# PiModulos_-_Mayonaise.net
KiCad netlist of a schematic drawn in Altium Designer
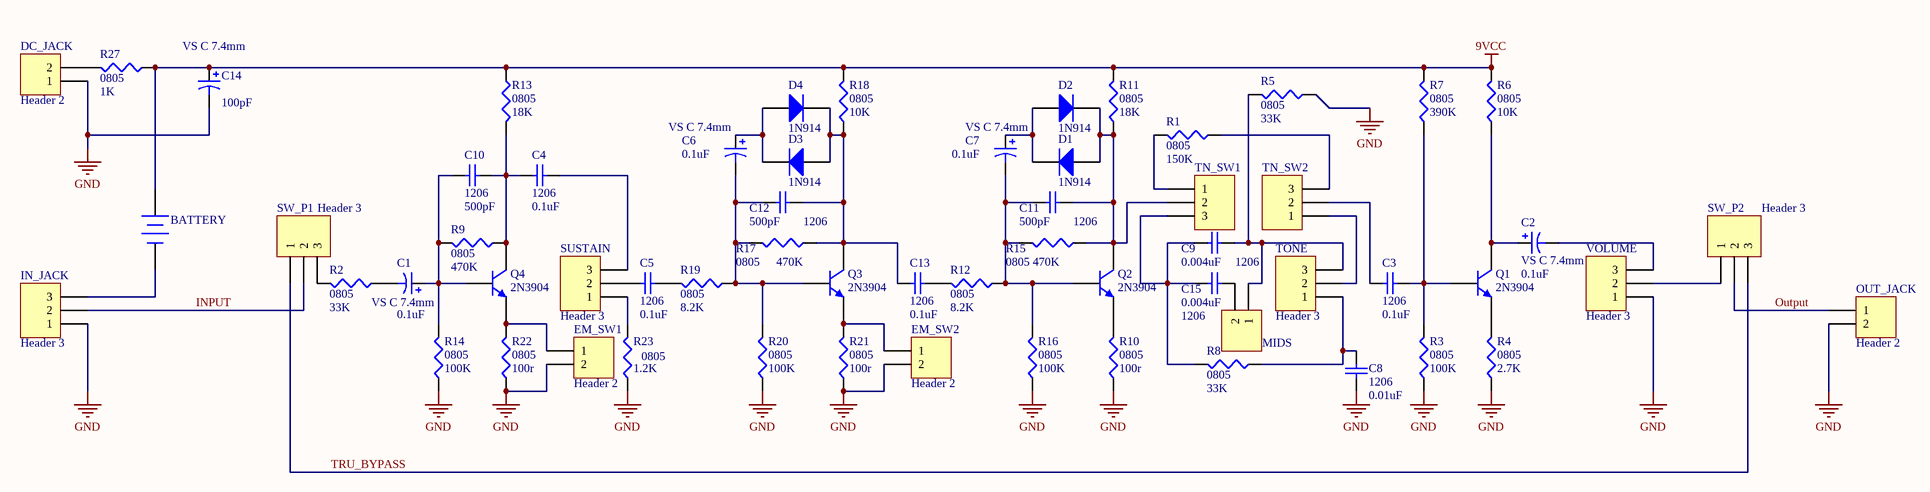
[diagram p0: PiModulos - Mayonaise.SchDoc]

(export (version "E")
  (design (tool "Eeschema 10.0.6"))
  (components
    (comp (ref "BATTERY")
      (value "Battery")
      (footprint "BAT-2")
      (description "Multicell Battery")
      (fields (field (name "PUBLISHER") "Altium Limited"))
      (libsource (lib "Miscellaneous Devices") (part "Battery"))
    )
    (comp (ref "C1")
      (value "VS C 7.4mm")
      (footprint "Panasonic VS C")
      (description "Polarized Capacitor (Radial)")
      (fields (field (name "ALTIUM_VALUE") "0.1uF") (field (name "PUBLISHER") "Altium Limited"))
      (libsource (lib "Miscellaneous Devices") (part "Cap Pol1"))
    )
    (comp (ref "C2")
      (value "VS C 7.4mm")
      (footprint "Panasonic VS C")
      (description "Polarized Capacitor (Radial)")
      (fields (field (name "ALTIUM_VALUE") "0.1uF") (field (name "PUBLISHER") "Altium Limited"))
      (libsource (lib "Miscellaneous Devices") (part "Cap Pol1"))
    )
    (comp (ref "C3")
      (value "1206")
      (footprint "C1206")
      (description "Capacitor (Semiconductor SIM Model)")
      (fields (field (name "ALTIUM_VALUE") "0.1uF") (field (name "PUBLISHER") "Altium Limited"))
      (libsource (lib "Miscellaneous Devices") (part "Cap Semi"))
    )
    (comp (ref "C4")
      (value "1206")
      (footprint "C1206")
      (description "Capacitor (Semiconductor SIM Model)")
      (fields (field (name "ALTIUM_VALUE") "0.1uF") (field (name "PUBLISHER") "Altium Limited"))
      (libsource (lib "Miscellaneous Devices") (part "Cap Semi"))
    )
    (comp (ref "C5")
      (value "1206")
      (footprint "C1206")
      (description "Capacitor (Semiconductor SIM Model)")
      (fields (field (name "ALTIUM_VALUE") "0.1uF") (field (name "PUBLISHER") "Altium Limited"))
      (libsource (lib "Miscellaneous Devices") (part "Cap Semi"))
    )
    (comp (ref "C6")
      (value "VS C 7.4mm")
      (footprint "Panasonic VS C")
      (description "Polarized Capacitor (Radial)")
      (fields (field (name "ALTIUM_VALUE") "0.1uF") (field (name "PUBLISHER") "Altium Limited"))
      (libsource (lib "Miscellaneous Devices") (part "Cap Pol1"))
    )
    (comp (ref "C7")
      (value "VS C 7.4mm")
      (footprint "Panasonic VS C")
      (description "Polarized Capacitor (Radial)")
      (fields (field (name "ALTIUM_VALUE") "0.1uF") (field (name "PUBLISHER") "Altium Limited"))
      (libsource (lib "Miscellaneous Devices") (part "Cap Pol1"))
    )
    (comp (ref "C8")
      (value "1206")
      (footprint "C1206")
      (description "Capacitor (Semiconductor SIM Model)")
      (fields (field (name "ALTIUM_VALUE") "0.01uF") (field (name "PUBLISHER") "Altium Limited"))
      (libsource (lib "Miscellaneous Devices") (part "Cap Semi"))
    )
    (comp (ref "C9")
      (value "1206")
      (footprint "C1206")
      (description "Capacitor (Semiconductor SIM Model)")
      (fields (field (name "ALTIUM_VALUE") "0.004uF") (field (name "PUBLISHER") "Altium Limited"))
      (libsource (lib "Miscellaneous Devices") (part "Cap Semi"))
    )
    (comp (ref "C10")
      (value "1206")
      (footprint "C1206")
      (description "Capacitor (Semiconductor SIM Model)")
      (fields (field (name "ALTIUM_VALUE") "500pF") (field (name "PUBLISHER") "Altium Limited"))
      (libsource (lib "Miscellaneous Devices") (part "Cap Semi"))
    )
    (comp (ref "C11")
      (value "1206")
      (footprint "C1206")
      (description "Capacitor (Semiconductor SIM Model)")
      (fields (field (name "ALTIUM_VALUE") "500pF") (field (name "PUBLISHER") "Altium Limited"))
      (libsource (lib "Miscellaneous Devices") (part "Cap Semi"))
    )
    (comp (ref "C12")
      (value "1206")
      (footprint "C1206")
      (description "Capacitor (Semiconductor SIM Model)")
      (fields (field (name "ALTIUM_VALUE") "500pF") (field (name "PUBLISHER") "Altium Limited"))
      (libsource (lib "Miscellaneous Devices") (part "Cap Semi"))
    )
    (comp (ref "C13")
      (value "1206")
      (footprint "C1206")
      (description "Capacitor (Semiconductor SIM Model)")
      (fields (field (name "ALTIUM_VALUE") "0.1uF") (field (name "PUBLISHER") "Altium Limited"))
      (libsource (lib "Miscellaneous Devices") (part "Cap Semi"))
    )
    (comp (ref "C14")
      (value "VS C 7.4mm")
      (footprint "Panasonic VS C")
      (description "Polarized Capacitor (Radial)")
      (fields (field (name "ALTIUM_VALUE") "100pF") (field (name "PUBLISHER") "Altium Limited"))
      (libsource (lib "Miscellaneous Devices") (part "Cap Pol1"))
    )
    (comp (ref "C15")
      (value "1206")
      (footprint "C1206")
      (description "Capacitor (Semiconductor SIM Model)")
      (fields (field (name "ALTIUM_VALUE") "0.004uF") (field (name "PUBLISHER") "Altium Limited"))
      (libsource (lib "Miscellaneous Devices") (part "Cap Semi"))
    )
    (comp (ref "D1")
      (value "1N914")
      (footprint "DO-35")
      (description "High Conductance Fast Diode")
      (fields (field (name "PUBLISHER") "Altium Limited"))
      (libsource (lib "Miscellaneous Devices") (part "Diode 1N914"))
    )
    (comp (ref "D2")
      (value "1N914")
      (footprint "DO-35")
      (description "High Conductance Fast Diode")
      (fields (field (name "PUBLISHER") "Altium Limited"))
      (libsource (lib "Miscellaneous Devices") (part "Diode 1N914"))
    )
    (comp (ref "D3")
      (value "1N914")
      (footprint "DO-35")
      (description "High Conductance Fast Diode")
      (fields (field (name "PUBLISHER") "Altium Limited"))
      (libsource (lib "Miscellaneous Devices") (part "Diode 1N914"))
    )
    (comp (ref "D4")
      (value "1N914")
      (footprint "DO-35")
      (description "High Conductance Fast Diode")
      (fields (field (name "PUBLISHER") "Altium Limited"))
      (libsource (lib "Miscellaneous Devices") (part "Diode 1N914"))
    )
    (comp (ref "DC_JACK")
      (value "Header 2")
      (footprint "HDR1X2")
      (description "Header, 2-Pin")
      (fields (field (name "PUBLISHER") "Altium Limited"))
      (libsource (lib "Miscellaneous Connectors") (part "Header 2"))
    )
    (comp (ref "EM_SW1")
      (value "Header 2")
      (footprint "HDR1X2")
      (description "Header, 2-Pin")
      (fields (field (name "PUBLISHER") "Altium Limited"))
      (libsource (lib "") (part "Header 2_2"))
    )
    (comp (ref "EM_SW2")
      (value "Header 2")
      (footprint "HDR1X2")
      (description "Header, 2-Pin")
      (fields (field (name "PUBLISHER") "Altium Limited"))
      (libsource (lib "") (part "Header 2_2"))
    )
    (comp (ref "IN_JACK")
      (value "Header 3")
      (footprint "HDR1X3")
      (description "Header, 3-Pin")
      (fields (field (name "PUBLISHER") "Altium Limited"))
      (libsource (lib "Miscellaneous Connectors") (part "Header 3"))
    )
    (comp (ref "MIDS")
      (value "Header 2")
      (footprint "HDR1X2")
      (description "Header, 2-Pin")
      (fields (field (name "PUBLISHER") "Altium Limited"))
      (libsource (lib "") (part "Header 2_1"))
    )
    (comp (ref "OUT_JACK")
      (value "Header 2")
      (footprint "HDR1X2")
      (description "Header, 2-Pin")
      (fields (field (name "PUBLISHER") "Altium Limited"))
      (libsource (lib "") (part "Header 2_2"))
    )
    (comp (ref "Q1")
      (value "2N3904")
      (footprint "TO-92A")
      (description "NPN General Purpose Amplifier")
      (fields (field (name "PUBLISHER") "Altium Limited"))
      (libsource (lib "Miscellaneous Devices") (part "2N3904"))
    )
    (comp (ref "Q2")
      (value "2N3904")
      (footprint "TO-92A")
      (description "NPN General Purpose Amplifier")
      (fields (field (name "PUBLISHER") "Altium Limited"))
      (libsource (lib "Miscellaneous Devices") (part "2N3904"))
    )
    (comp (ref "Q3")
      (value "2N3904")
      (footprint "TO-92A")
      (description "NPN General Purpose Amplifier")
      (fields (field (name "PUBLISHER") "Altium Limited"))
      (libsource (lib "Miscellaneous Devices") (part "2N3904"))
    )
    (comp (ref "Q4")
      (value "2N3904")
      (footprint "TO-92A")
      (description "NPN General Purpose Amplifier")
      (fields (field (name "PUBLISHER") "Altium Limited"))
      (libsource (lib "Miscellaneous Devices") (part "2N3904"))
    )
    (comp (ref "R1")
      (value "0805")
      (footprint "SM 0805 - gap trimmed")
      (description "Resistor")
      (fields (field (name "ALTIUM_VALUE") "150K") (field (name "PUBLISHER") "Altium Limited"))
      (libsource (lib "Miscellaneous Devices") (part "Res3"))
    )
    (comp (ref "R2")
      (value "0805")
      (footprint "SM 0805 - gap trimmed")
      (description "Resistor")
      (fields (field (name "ALTIUM_VALUE") "33K") (field (name "PUBLISHER") "Altium Limited"))
      (libsource (lib "Miscellaneous Devices") (part "Res3"))
    )
    (comp (ref "R3")
      (value "0805")
      (footprint "SM 0805 - gap trimmed")
      (description "Resistor")
      (fields (field (name "ALTIUM_VALUE") "100K") (field (name "PUBLISHER") "Altium Limited"))
      (libsource (lib "Miscellaneous Devices") (part "Res3"))
    )
    (comp (ref "R4")
      (value "0805")
      (footprint "SM 0805 - gap trimmed")
      (description "Resistor")
      (fields (field (name "ALTIUM_VALUE") "2.7K") (field (name "PUBLISHER") "Altium Limited"))
      (libsource (lib "Miscellaneous Devices") (part "Res3"))
    )
    (comp (ref "R5")
      (value "0805")
      (footprint "SM 0805 - gap trimmed")
      (description "Resistor")
      (fields (field (name "ALTIUM_VALUE") "33K") (field (name "PUBLISHER") "Altium Limited"))
      (libsource (lib "Miscellaneous Devices") (part "Res3"))
    )
    (comp (ref "R6")
      (value "0805")
      (footprint "SM 0805 - gap trimmed")
      (description "Resistor")
      (fields (field (name "ALTIUM_VALUE") "10K") (field (name "PUBLISHER") "Altium Limited"))
      (libsource (lib "Miscellaneous Devices") (part "Res3"))
    )
    (comp (ref "R7")
      (value "0805")
      (footprint "SM 0805 - gap trimmed")
      (description "Resistor")
      (fields (field (name "ALTIUM_VALUE") "390K") (field (name "PUBLISHER") "Altium Limited"))
      (libsource (lib "Miscellaneous Devices") (part "Res3"))
    )
    (comp (ref "R8")
      (value "0805")
      (footprint "SM 0805 - gap trimmed")
      (description "Resistor")
      (fields (field (name "ALTIUM_VALUE") "33K") (field (name "PUBLISHER") "Altium Limited"))
      (libsource (lib "Miscellaneous Devices") (part "Res3"))
    )
    (comp (ref "R9")
      (value "0805")
      (footprint "SM 0805 - gap trimmed")
      (description "Resistor")
      (fields (field (name "ALTIUM_VALUE") "470K") (field (name "PUBLISHER") "Altium Limited"))
      (libsource (lib "Miscellaneous Devices") (part "Res3"))
    )
    (comp (ref "R10")
      (value "0805")
      (footprint "SM 0805 - gap trimmed")
      (description "Resistor")
      (fields (field (name "ALTIUM_VALUE") "100r") (field (name "PUBLISHER") "Altium Limited"))
      (libsource (lib "Miscellaneous Devices") (part "Res3"))
    )
    (comp (ref "R11")
      (value "0805")
      (footprint "SM 0805 - gap trimmed")
      (description "Resistor")
      (fields (field (name "ALTIUM_VALUE") "18K") (field (name "PUBLISHER") "Altium Limited"))
      (libsource (lib "Miscellaneous Devices") (part "Res3"))
    )
    (comp (ref "R12")
      (value "0805")
      (footprint "SM 0805 - gap trimmed")
      (description "Resistor")
      (fields (field (name "ALTIUM_VALUE") "8.2K") (field (name "PUBLISHER") "Altium Limited"))
      (libsource (lib "Miscellaneous Devices") (part "Res3"))
    )
    (comp (ref "R13")
      (value "0805")
      (footprint "SM 0805 - gap trimmed")
      (description "Resistor")
      (fields (field (name "ALTIUM_VALUE") "18K") (field (name "PUBLISHER") "Altium Limited"))
      (libsource (lib "Miscellaneous Devices") (part "Res3"))
    )
    (comp (ref "R14")
      (value "0805")
      (footprint "SM 0805 - gap trimmed")
      (description "Resistor")
      (fields (field (name "ALTIUM_VALUE") "100K") (field (name "PUBLISHER") "Altium Limited"))
      (libsource (lib "Miscellaneous Devices") (part "Res3"))
    )
    (comp (ref "R15")
      (value "0805")
      (footprint "SM 0805 - gap trimmed")
      (description "Resistor")
      (fields (field (name "ALTIUM_VALUE") "470K") (field (name "PUBLISHER") "Altium Limited"))
      (libsource (lib "Miscellaneous Devices") (part "Res3"))
    )
    (comp (ref "R16")
      (value "0805")
      (footprint "SM 0805 - gap trimmed")
      (description "Resistor")
      (fields (field (name "ALTIUM_VALUE") "100K") (field (name "PUBLISHER") "Altium Limited"))
      (libsource (lib "Miscellaneous Devices") (part "Res3"))
    )
    (comp (ref "R17")
      (value "0805")
      (footprint "SM 0805 - gap trimmed")
      (description "Resistor")
      (fields (field (name "ALTIUM_VALUE") "470K") (field (name "PUBLISHER") "Altium Limited"))
      (libsource (lib "Miscellaneous Devices") (part "Res3"))
    )
    (comp (ref "R18")
      (value "0805")
      (footprint "SM 0805 - gap trimmed")
      (description "Resistor")
      (fields (field (name "ALTIUM_VALUE") "10K") (field (name "PUBLISHER") "Altium Limited"))
      (libsource (lib "Miscellaneous Devices") (part "Res3"))
    )
    (comp (ref "R19")
      (value "0805")
      (footprint "SM 0805 - gap trimmed")
      (description "Resistor")
      (fields (field (name "ALTIUM_VALUE") "8.2K") (field (name "PUBLISHER") "Altium Limited"))
      (libsource (lib "Miscellaneous Devices") (part "Res3"))
    )
    (comp (ref "R20")
      (value "0805")
      (footprint "SM 0805 - gap trimmed")
      (description "Resistor")
      (fields (field (name "ALTIUM_VALUE") "100K") (field (name "PUBLISHER") "Altium Limited"))
      (libsource (lib "Miscellaneous Devices") (part "Res3"))
    )
    (comp (ref "R21")
      (value "0805")
      (footprint "SM 0805 - gap trimmed")
      (description "Resistor")
      (fields (field (name "ALTIUM_VALUE") "100r") (field (name "PUBLISHER") "Altium Limited"))
      (libsource (lib "Miscellaneous Devices") (part "Res3"))
    )
    (comp (ref "R22")
      (value "0805")
      (footprint "SM 0805 - gap trimmed")
      (description "Resistor")
      (fields (field (name "ALTIUM_VALUE") "100r") (field (name "PUBLISHER") "Altium Limited"))
      (libsource (lib "Miscellaneous Devices") (part "Res3"))
    )
    (comp (ref "R23")
      (value "0805")
      (footprint "SM 0805 - gap trimmed")
      (description "Resistor")
      (fields (field (name "ALTIUM_VALUE") "1.2K") (field (name "PUBLISHER") "Altium Limited"))
      (libsource (lib "Miscellaneous Devices") (part "Res3"))
    )
    (comp (ref "R27")
      (value "0805")
      (footprint "SM 0805 - gap trimmed")
      (description "Resistor")
      (fields (field (name "ALTIUM_VALUE") "1K") (field (name "PUBLISHER") "Altium Limited"))
      (libsource (lib "Miscellaneous Devices") (part "Res3"))
    )
    (comp (ref "SUSTAIN")
      (value "Header 3")
      (footprint "HDR1X3")
      (description "Header, 3-Pin")
      (fields (field (name "PUBLISHER") "Altium Limited"))
      (libsource (lib "Miscellaneous Connectors") (part "Header 3"))
    )
    (comp (ref "SW_P1")
      (value "Header 3")
      (footprint "HDR1X3")
      (description "Header, 3-Pin")
      (fields (field (name "PUBLISHER") "Altium Limited"))
      (libsource (lib "") (part "Header 3_1"))
    )
    (comp (ref "SW_P2")
      (value "Header 3")
      (footprint "HDR1X3")
      (description "Header, 3-Pin")
      (fields (field (name "PUBLISHER") "Altium Limited"))
      (libsource (lib "") (part "Header 3_1"))
    )
    (comp (ref "TN_SW1")
      (value "Header 3")
      (footprint "HDR1X3")
      (description "Header, 3-Pin")
      (fields (field (name "PUBLISHER") "Altium Limited"))
      (libsource (lib "") (part "Header 3_2"))
    )
    (comp (ref "TN_SW2")
      (value "Header 3")
      (footprint "HDR1X3")
      (description "Header, 3-Pin")
      (fields (field (name "PUBLISHER") "Altium Limited"))
      (libsource (lib "Miscellaneous Connectors") (part "Header 3"))
    )
    (comp (ref "TONE")
      (value "Header 3")
      (footprint "HDR1X3")
      (description "Header, 3-Pin")
      (fields (field (name "PUBLISHER") "Altium Limited"))
      (libsource (lib "Miscellaneous Connectors") (part "Header 3"))
    )
    (comp (ref "VOLUME")
      (value "Header 3")
      (footprint "HDR1X3")
      (description "Header, 3-Pin")
      (fields (field (name "PUBLISHER") "Altium Limited"))
      (libsource (lib "Miscellaneous Connectors") (part "Header 3"))
    )
  )
  (nets
    (net (code "1") (name "/INPUT") (class "Default")
      (node (ref "IN_JACK") (pin "2") (pinfunction "2_2") (pintype "passive"))
      (node (ref "SW_P1") (pin "2") (pinfunction "2_2") (pintype "passive"))
    )
    (net (code "2") (name "/Output") (class "Default")
      (node (ref "OUT_JACK") (pin "1") (pinfunction "1_1") (pintype "passive"))
      (node (ref "SW_P2") (pin "2") (pinfunction "2_2") (pintype "passive"))
    )
    (net (code "3") (name "/TRU_BYPASS") (class "Default")
      (node (ref "SW_P1") (pin "1") (pinfunction "1_1") (pintype "passive"))
      (node (ref "SW_P2") (pin "3") (pinfunction "3_3") (pintype "passive"))
    )
    (net (code "4") (name "9VCC") (class "Default")
      (node (ref "BATTERY") (pin "1") (pinfunction "+_1") (pintype "passive"))
      (node (ref "C14") (pin "1") (pinfunction "1_1") (pintype "passive"))
      (node (ref "R11") (pin "2") (pinfunction "2_2") (pintype "passive"))
      (node (ref "R13") (pin "1") (pinfunction "1_1") (pintype "passive"))
      (node (ref "R18") (pin "2") (pinfunction "2_2") (pintype "passive"))
      (node (ref "R27") (pin "1") (pinfunction "1_1") (pintype "passive"))
      (node (ref "R6") (pin "2") (pinfunction "2_2") (pintype "passive"))
      (node (ref "R7") (pin "2") (pinfunction "2_2") (pintype "passive"))
    )
    (net (code "5") (name "GND") (class "Default")
      (node (ref "C14") (pin "2") (pinfunction "2_2") (pintype "passive"))
      (node (ref "C8") (pin "1") (pinfunction "1_1") (pintype "passive"))
      (node (ref "DC_JACK") (pin "1") (pinfunction "1_1") (pintype "passive"))
      (node (ref "EM_SW1") (pin "2") (pinfunction "2_2") (pintype "passive"))
      (node (ref "EM_SW2") (pin "2") (pinfunction "2_2") (pintype "passive"))
      (node (ref "IN_JACK") (pin "1") (pinfunction "1_1") (pintype "passive"))
      (node (ref "OUT_JACK") (pin "2") (pinfunction "2_2") (pintype "passive"))
      (node (ref "R10") (pin "1") (pinfunction "1_1") (pintype "passive"))
      (node (ref "R14") (pin "1") (pinfunction "1_1") (pintype "passive"))
      (node (ref "R16") (pin "1") (pinfunction "1_1") (pintype "passive"))
      (node (ref "R20") (pin "1") (pinfunction "1_1") (pintype "passive"))
      (node (ref "R21") (pin "1") (pinfunction "1_1") (pintype "passive"))
      (node (ref "R22") (pin "1") (pinfunction "1_1") (pintype "passive"))
      (node (ref "R23") (pin "1") (pinfunction "1_1") (pintype "passive"))
      (node (ref "R3") (pin "1") (pinfunction "1_1") (pintype "passive"))
      (node (ref "R4") (pin "1") (pinfunction "1_1") (pintype "passive"))
      (node (ref "R5") (pin "1") (pinfunction "1_1") (pintype "passive"))
      (node (ref "VOLUME") (pin "1") (pinfunction "1_1") (pintype "passive"))
    )
    (net (code "6") (name "Net-(BATTERY--)") (class "Default")
      (node (ref "BATTERY") (pin "2") (pinfunction "-_2") (pintype "passive"))
      (node (ref "IN_JACK") (pin "3") (pinfunction "3_3") (pintype "passive"))
    )
    (net (code "7") (name "Net-(C1-Pad2)") (class "Default")
      (node (ref "C1") (pin "2") (pinfunction "2_2") (pintype "passive"))
      (node (ref "R2") (pin "1") (pinfunction "1_1") (pintype "passive"))
    )
    (net (code "8") (name "Net-(C2-Pad2)") (class "Default")
      (node (ref "C2") (pin "2") (pinfunction "2_2") (pintype "passive"))
      (node (ref "VOLUME") (pin "3") (pinfunction "3_3") (pintype "passive"))
    )
    (net (code "9") (name "Net-(C3-Pad1)") (class "Default")
      (node (ref "C3") (pin "1") (pinfunction "1_1") (pintype "passive"))
      (node (ref "TN_SW2") (pin "2") (pinfunction "2_2") (pintype "passive"))
    )
    (net (code "10") (name "Net-(C4-Pad2)") (class "Default")
      (node (ref "C4") (pin "2") (pinfunction "2_2") (pintype "passive"))
      (node (ref "SUSTAIN") (pin "3") (pinfunction "3_3") (pintype "passive"))
    )
    (net (code "11") (name "Net-(C5-Pad1)") (class "Default")
      (node (ref "C5") (pin "1") (pinfunction "1_1") (pintype "passive"))
      (node (ref "SUSTAIN") (pin "2") (pinfunction "2_2") (pintype "passive"))
    )
    (net (code "12") (name "Net-(C5-Pad2)") (class "Default")
      (node (ref "C5") (pin "2") (pinfunction "2_2") (pintype "passive"))
      (node (ref "R19") (pin "2") (pinfunction "2_2") (pintype "passive"))
    )
    (net (code "13") (name "Net-(C8-Pad2)") (class "Default")
      (node (ref "C8") (pin "2") (pinfunction "2_2") (pintype "passive"))
      (node (ref "R8") (pin "1") (pinfunction "1_1") (pintype "passive"))
      (node (ref "TONE") (pin "1") (pinfunction "1_1") (pintype "passive"))
    )
    (net (code "14") (name "Net-(C9-Pad2)") (class "Default")
      (node (ref "C9") (pin "2") (pinfunction "2_2") (pintype "passive"))
      (node (ref "MIDS") (pin "1") (pinfunction "1_1") (pintype "passive"))
      (node (ref "R5") (pin "2") (pinfunction "2_2") (pintype "passive"))
      (node (ref "TONE") (pin "3") (pinfunction "3_3") (pintype "passive"))
    )
    (net (code "15") (name "Net-(C13-Pad2)") (class "Default")
      (node (ref "C13") (pin "2") (pinfunction "2_2") (pintype "passive"))
      (node (ref "R12") (pin "2") (pinfunction "2_2") (pintype "passive"))
    )
    (net (code "16") (name "Net-(C15-Pad1)") (class "Default")
      (node (ref "C15") (pin "1") (pinfunction "1_1") (pintype "passive"))
      (node (ref "C9") (pin "1") (pinfunction "1_1") (pintype "passive"))
      (node (ref "R8") (pin "2") (pinfunction "2_2") (pintype "passive"))
      (node (ref "TN_SW1") (pin "3") (pinfunction "3_3") (pintype "passive"))
    )
    (net (code "17") (name "Net-(C15-Pad2)") (class "Default")
      (node (ref "C15") (pin "2") (pinfunction "2_2") (pintype "passive"))
      (node (ref "MIDS") (pin "2") (pinfunction "2_2") (pintype "passive"))
    )
    (net (code "18") (name "Net-(D1-A)") (class "Default")
      (node (ref "C11") (pin "2") (pinfunction "2_2") (pintype "passive"))
      (node (ref "D1") (pin "1") (pinfunction "A_1") (pintype "passive"))
      (node (ref "D2") (pin "2") (pinfunction "K_2") (pintype "passive"))
      (node (ref "Q2") (pin "3") (pinfunction "C_3") (pintype "passive"))
      (node (ref "R11") (pin "1") (pinfunction "1_1") (pintype "passive"))
      (node (ref "R15") (pin "1") (pinfunction "1_1") (pintype "passive"))
      (node (ref "TN_SW1") (pin "2") (pinfunction "2_2") (pintype "passive"))
    )
    (net (code "19") (name "Net-(D1-K)") (class "Default")
      (node (ref "C7") (pin "1") (pinfunction "1_1") (pintype "passive"))
      (node (ref "D1") (pin "2") (pinfunction "K_2") (pintype "passive"))
      (node (ref "D2") (pin "1") (pinfunction "A_1") (pintype "passive"))
    )
    (net (code "20") (name "Net-(D3-A)") (class "Default")
      (node (ref "C12") (pin "2") (pinfunction "2_2") (pintype "passive"))
      (node (ref "C13") (pin "1") (pinfunction "1_1") (pintype "passive"))
      (node (ref "D3") (pin "1") (pinfunction "A_1") (pintype "passive"))
      (node (ref "D4") (pin "2") (pinfunction "K_2") (pintype "passive"))
      (node (ref "Q3") (pin "3") (pinfunction "C_3") (pintype "passive"))
      (node (ref "R17") (pin "1") (pinfunction "1_1") (pintype "passive"))
      (node (ref "R18") (pin "1") (pinfunction "1_1") (pintype "passive"))
    )
    (net (code "21") (name "Net-(D3-K)") (class "Default")
      (node (ref "C6") (pin "1") (pinfunction "1_1") (pintype "passive"))
      (node (ref "D3") (pin "2") (pinfunction "K_2") (pintype "passive"))
      (node (ref "D4") (pin "1") (pinfunction "A_1") (pintype "passive"))
    )
    (net (code "22") (name "Net-(DC_JACK-Pad2)") (class "Default")
      (node (ref "DC_JACK") (pin "2") (pinfunction "2_2") (pintype "passive"))
      (node (ref "R27") (pin "2") (pinfunction "2_2") (pintype "passive"))
    )
    (net (code "23") (name "Net-(Q1-B)") (class "Default")
      (node (ref "C3") (pin "2") (pinfunction "2_2") (pintype "passive"))
      (node (ref "Q1") (pin "2") (pinfunction "B_2") (pintype "passive"))
      (node (ref "R3") (pin "2") (pinfunction "2_2") (pintype "passive"))
      (node (ref "R7") (pin "1") (pinfunction "1_1") (pintype "passive"))
    )
    (net (code "24") (name "Net-(Q1-C)") (class "Default")
      (node (ref "C2") (pin "1") (pinfunction "1_1") (pintype "passive"))
      (node (ref "Q1") (pin "3") (pinfunction "C_3") (pintype "passive"))
      (node (ref "R6") (pin "1") (pinfunction "1_1") (pintype "passive"))
    )
    (net (code "25") (name "Net-(Q1-E)") (class "Default")
      (node (ref "Q1") (pin "1") (pinfunction "E_1") (pintype "passive"))
      (node (ref "R4") (pin "2") (pinfunction "2_2") (pintype "passive"))
    )
    (net (code "26") (name "Net-(Q2-B)") (class "Default")
      (node (ref "C11") (pin "1") (pinfunction "1_1") (pintype "passive"))
      (node (ref "C7") (pin "2") (pinfunction "2_2") (pintype "passive"))
      (node (ref "Q2") (pin "2") (pinfunction "B_2") (pintype "passive"))
      (node (ref "R12") (pin "1") (pinfunction "1_1") (pintype "passive"))
      (node (ref "R15") (pin "2") (pinfunction "2_2") (pintype "passive"))
      (node (ref "R16") (pin "2") (pinfunction "2_2") (pintype "passive"))
    )
    (net (code "27") (name "Net-(Q2-E)") (class "Default")
      (node (ref "Q2") (pin "1") (pinfunction "E_1") (pintype "passive"))
      (node (ref "R10") (pin "2") (pinfunction "2_2") (pintype "passive"))
    )
    (net (code "28") (name "Net-(Q3-B)") (class "Default")
      (node (ref "C12") (pin "1") (pinfunction "1_1") (pintype "passive"))
      (node (ref "C6") (pin "2") (pinfunction "2_2") (pintype "passive"))
      (node (ref "Q3") (pin "2") (pinfunction "B_2") (pintype "passive"))
      (node (ref "R17") (pin "2") (pinfunction "2_2") (pintype "passive"))
      (node (ref "R19") (pin "1") (pinfunction "1_1") (pintype "passive"))
      (node (ref "R20") (pin "2") (pinfunction "2_2") (pintype "passive"))
    )
    (net (code "29") (name "Net-(Q3-E)") (class "Default")
      (node (ref "EM_SW2") (pin "1") (pinfunction "1_1") (pintype "passive"))
      (node (ref "Q3") (pin "1") (pinfunction "E_1") (pintype "passive"))
      (node (ref "R21") (pin "2") (pinfunction "2_2") (pintype "passive"))
    )
    (net (code "30") (name "Net-(Q4-B)") (class "Default")
      (node (ref "C1") (pin "1") (pinfunction "1_1") (pintype "passive"))
      (node (ref "C10") (pin "1") (pinfunction "1_1") (pintype "passive"))
      (node (ref "Q4") (pin "2") (pinfunction "B_2") (pintype "passive"))
      (node (ref "R14") (pin "2") (pinfunction "2_2") (pintype "passive"))
      (node (ref "R9") (pin "2") (pinfunction "2_2") (pintype "passive"))
    )
    (net (code "31") (name "Net-(Q4-C)") (class "Default")
      (node (ref "C10") (pin "2") (pinfunction "2_2") (pintype "passive"))
      (node (ref "C4") (pin "1") (pinfunction "1_1") (pintype "passive"))
      (node (ref "Q4") (pin "3") (pinfunction "C_3") (pintype "passive"))
      (node (ref "R13") (pin "2") (pinfunction "2_2") (pintype "passive"))
      (node (ref "R9") (pin "1") (pinfunction "1_1") (pintype "passive"))
    )
    (net (code "32") (name "Net-(Q4-E)") (class "Default")
      (node (ref "EM_SW1") (pin "1") (pinfunction "1_1") (pintype "passive"))
      (node (ref "Q4") (pin "1") (pinfunction "E_1") (pintype "passive"))
      (node (ref "R22") (pin "2") (pinfunction "2_2") (pintype "passive"))
    )
    (net (code "33") (name "Net-(R1-Pad1)") (class "Default")
      (node (ref "R1") (pin "1") (pinfunction "1_1") (pintype "passive"))
      (node (ref "TN_SW2") (pin "3") (pinfunction "3_3") (pintype "passive"))
    )
    (net (code "34") (name "Net-(R1-Pad2)") (class "Default")
      (node (ref "R1") (pin "2") (pinfunction "2_2") (pintype "passive"))
      (node (ref "TN_SW1") (pin "1") (pinfunction "1_1") (pintype "passive"))
    )
    (net (code "35") (name "Net-(R2-Pad2)") (class "Default")
      (node (ref "R2") (pin "2") (pinfunction "2_2") (pintype "passive"))
      (node (ref "SW_P1") (pin "3") (pinfunction "3_3") (pintype "passive"))
    )
    (net (code "36") (name "Net-(R23-Pad2)") (class "Default")
      (node (ref "R23") (pin "2") (pinfunction "2_2") (pintype "passive"))
      (node (ref "SUSTAIN") (pin "1") (pinfunction "1_1") (pintype "passive"))
    )
    (net (code "37") (name "Net-(SW_P2-Pad1)") (class "Default")
      (node (ref "SW_P2") (pin "1") (pinfunction "1_1") (pintype "passive"))
      (node (ref "VOLUME") (pin "2") (pinfunction "2_2") (pintype "passive"))
    )
    (net (code "38") (name "Net-(TN_SW2-Pad1)") (class "Default")
      (node (ref "TN_SW2") (pin "1") (pinfunction "1_1") (pintype "passive"))
      (node (ref "TONE") (pin "2") (pinfunction "2_2") (pintype "passive"))
    )
  )
)
